# ife18_TS_BMS_Master.net
KiCad netlist of a schematic drawn in Altium Designer
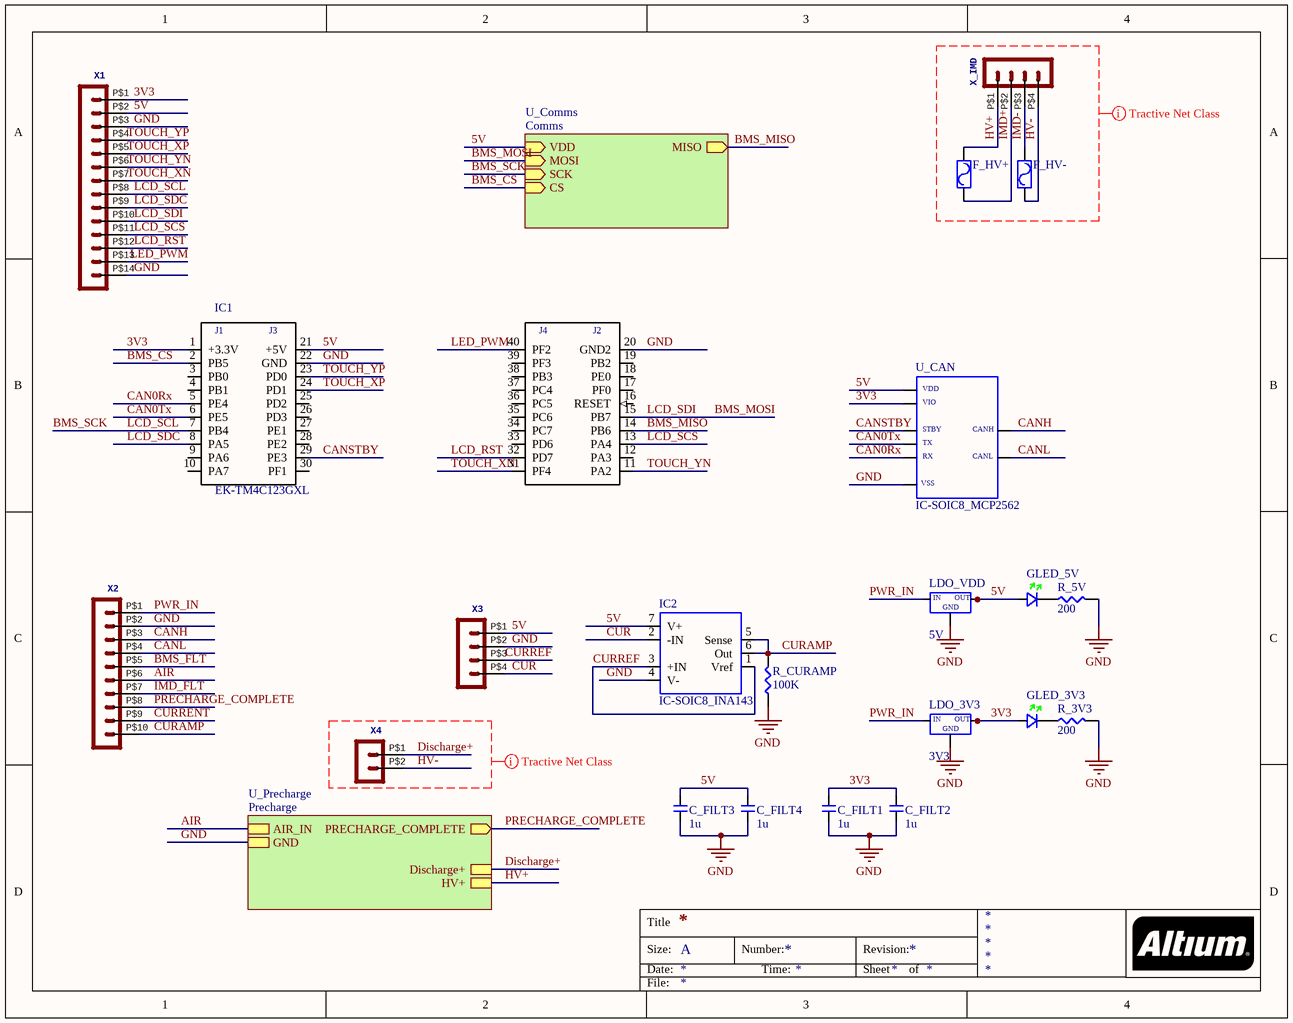
[diagram p0: ife18_TS_BMS_Master.SchDoc]

(export (version "E")
  (design (tool "Eeschema 10.0.6"))
  (components
    (comp (ref "C_FILT1")
      (value "1u")
      (footprint "CAP-0603")
      (libsource (lib "altium-import") (part "root_1_CAP-0603_"))
    )
    (comp (ref "C_FILT2")
      (value "1u")
      (footprint "CAP-0603")
      (libsource (lib "altium-import") (part "root_1_CAP-0603_"))
    )
    (comp (ref "C_FILT3")
      (value "1u")
      (footprint "CAP-0603")
      (libsource (lib "altium-import") (part "root_1_CAP-0603_"))
    )
    (comp (ref "C_FILT4")
      (value "1u")
      (footprint "CAP-0603")
      (libsource (lib "altium-import") (part "root_1_CAP-0603_"))
    )
    (comp (ref "F_HV+")
      (value "~")
      (footprint "FUSE3AG_354101")
      (libsource (lib "altium-import") (part "root_3_FUSE-354101_"))
    )
    (comp (ref "F_HV-")
      (value "~")
      (footprint "FUSE3AG_354101")
      (libsource (lib "altium-import") (part "root_3_FUSE-354101_"))
    )
    (comp (ref "GLED_3V3")
      (value "~")
      (footprint "LEDGREEN-0603")
      (libsource (lib "altium-import") (part "root_0_LEDGREEN-0603_"))
    )
    (comp (ref "GLED_5V")
      (value "~")
      (footprint "LEDGREEN-0603")
      (libsource (lib "altium-import") (part "root_0_LEDGREEN-0603_"))
    )
    (comp (ref "IC1")
      (value "EK-TM4C123GXL")
      (footprint "TM4C123LAUNCHPAD")
      (description "Evaluation Kit For ARM Cortex-M4F-based Microcontrollers")
      (fields (field (name "MF") "Texas Instruments"))
      (libsource (lib "altium-import") (part "root_0_EK-TM4C123GXL_"))
    )
    (comp (ref "IC2")
      (value "IC-SOIC8_INA143")
      (footprint "SOIC8")
      (libsource (lib "altium-import") (part "root_0_IC-SOIC8_INA143_"))
    )
    (comp (ref "LDO_3V3")
      (value "3V3")
      (footprint "SOT223")
      (libsource (lib "altium-import") (part "root_0_LDO-SOT223_SPX1117_"))
    )
    (comp (ref "LDO_VDD")
      (value "5V")
      (footprint "SOT223")
      (libsource (lib "altium-import") (part "root_0_LDO-SOT223_SPX1117_"))
    )
    (comp (ref "R_3V3")
      (value "200")
      (footprint "RES-0603")
      (libsource (lib "altium-import") (part "root_0_RES-0603_"))
    )
    (comp (ref "R_5V")
      (value "200")
      (footprint "RES-0603")
      (libsource (lib "altium-import") (part "root_0_RES-0603_"))
    )
    (comp (ref "R_CURAMP")
      (value "100K")
      (footprint "RES-0603")
      (libsource (lib "altium-import") (part "root_1_RES-0603_"))
    )
    (comp (ref "U_CAN")
      (value "IC-SOIC8_MCP2562")
      (footprint "SOIC8")
      (libsource (lib "altium-import") (part "root_0_IC-SOIC8_MCP2562_"))
    )
    (comp (ref "X1")
      (value "Molex - Micro-Fit 3.0 Series connector,  3.00mm (0.118\") pitch header, 14 positions.")
      (footprint "43045-1418")
      (libsource (lib "altium-import") (part "root_0_mirrored_POS14_MF43045-1418_"))
    )
    (comp (ref "X2")
      (value "Molex - Micro-Fit 3.0 Series connector,  3.00mm (0.118\") pitch header, 10 positions.")
      (footprint "43045-1018")
      (libsource (lib "altium-import") (part "root_0_mirrored_POS10_MF43045-1018_"))
    )
    (comp (ref "X3")
      (value "Molex - Micro-Fit 3.0 Series connector,  3.00mm (0.118\") pitch header, 4 positions.")
      (footprint "43650-0424")
      (libsource (lib "altium-import") (part "root_0_mirrored_POS4_MF43650-0424_"))
    )
    (comp (ref "X4")
      (value "Molex - Micro-Fit 3.0 Series connector,  3.00mm (0.118\") pitch header, 2 positions.")
      (footprint "43650-0224")
      (libsource (lib "altium-import") (part "root_0_mirrored_POS2_MF43650-0224_"))
    )
    (comp (ref "X_IMD")
      (value "~")
      (footprint "43650-0424")
      (libsource (lib "ife19_Elec_Conn_Library") (part "POS4_MF43650-0424"))
    )
  )
  (nets
    (net (code "1") (name "/3V3") (class "Default")
      (node (ref "C_FILT1") (pin "2") (pinfunction "2_2") (pintype "passive"))
      (node (ref "C_FILT2") (pin "2") (pinfunction "2_2") (pintype "passive"))
      (node (ref "GLED_3V3") (pin "A") (pinfunction "A_A") (pintype "passive"))
      (node (ref "IC1") (pin "1") (pinfunction "+3.3V_1") (pintype "power_in"))
      (node (ref "LDO_3V3") (pin "2") (pinfunction "2_2") (pintype "passive"))
      (node (ref "LDO_3V3") (pin "4") (pinfunction "4_4") (pintype "passive"))
      (node (ref "U_CAN") (pin "5") (pinfunction "5_5") (pintype "passive"))
      (node (ref "X1") (pin "P$1") (pinfunction "1_P$1") (pintype "passive"))
    )
    (net (code "2") (name "/5V") (class "Default")
      (node (ref "C_FILT3") (pin "2") (pinfunction "2_2") (pintype "passive"))
      (node (ref "C_FILT4") (pin "2") (pinfunction "2_2") (pintype "passive"))
      (node (ref "GLED_5V") (pin "A") (pinfunction "A_A") (pintype "passive"))
      (node (ref "IC1") (pin "21") (pinfunction "+5V_21") (pintype "power_in"))
      (node (ref "IC2") (pin "7") (pinfunction "V+_7") (pintype "passive"))
      (node (ref "LDO_VDD") (pin "2") (pinfunction "2_2") (pintype "passive"))
      (node (ref "LDO_VDD") (pin "4") (pinfunction "4_4") (pintype "passive"))
      (node (ref "U_CAN") (pin "3") (pinfunction "3_3") (pintype "passive"))
      (node (ref "X1") (pin "P$2") (pinfunction "2_P$2") (pintype "passive"))
      (node (ref "X3") (pin "P$1") (pinfunction "1_P$1") (pintype "passive"))
    )
    (net (code "3") (name "/AIR") (class "Default")
      (node (ref "X2") (pin "P$6") (pinfunction "6_P$6") (pintype "passive"))
    )
    (net (code "4") (name "/BMS_CS") (class "Default")
      (node (ref "IC1") (pin "2") (pinfunction "PB5_2") (pintype "bidirectional"))
    )
    (net (code "5") (name "/BMS_FLT") (class "Default")
      (node (ref "X2") (pin "P$5") (pinfunction "5_P$5") (pintype "passive"))
    )
    (net (code "6") (name "/BMS_MISO") (class "Default")
      (node (ref "IC1") (pin "14") (pinfunction "PB6_14") (pintype "bidirectional"))
    )
    (net (code "7") (name "/BMS_MOSI") (class "Default")
      (node (ref "IC1") (pin "15") (pinfunction "PB7_15") (pintype "bidirectional"))
      (node (ref "X1") (pin "P$10") (pinfunction "10_P$10") (pintype "passive"))
    )
    (net (code "8") (name "/BMS_SCK") (class "Default")
      (node (ref "IC1") (pin "7") (pinfunction "PB4_7") (pintype "bidirectional"))
      (node (ref "X1") (pin "P$8") (pinfunction "8_P$8") (pintype "passive"))
    )
    (net (code "9") (name "/CAN0Rx") (class "Default")
      (node (ref "IC1") (pin "5") (pinfunction "PE4_5") (pintype "bidirectional"))
      (node (ref "U_CAN") (pin "4") (pinfunction "4_4") (pintype "passive"))
    )
    (net (code "10") (name "/CAN0Tx") (class "Default")
      (node (ref "IC1") (pin "6") (pinfunction "PE5_6") (pintype "bidirectional"))
      (node (ref "U_CAN") (pin "1") (pinfunction "1_1") (pintype "passive"))
    )
    (net (code "11") (name "/CANH") (class "Default")
      (node (ref "U_CAN") (pin "7") (pinfunction "7_7") (pintype "passive"))
      (node (ref "X2") (pin "P$3") (pinfunction "3_P$3") (pintype "passive"))
    )
    (net (code "12") (name "/CANL") (class "Default")
      (node (ref "U_CAN") (pin "6") (pinfunction "6_6") (pintype "passive"))
      (node (ref "X2") (pin "P$4") (pinfunction "4_P$4") (pintype "passive"))
    )
    (net (code "13") (name "/CANSTBY") (class "Default")
      (node (ref "IC1") (pin "29") (pinfunction "PE3_29") (pintype "bidirectional"))
      (node (ref "U_CAN") (pin "8") (pinfunction "8_8") (pintype "passive"))
    )
    (net (code "14") (name "/CUR") (class "Default")
      (node (ref "IC2") (pin "2") (pinfunction "-IN_2") (pintype "passive"))
      (node (ref "X3") (pin "P$4") (pinfunction "4_P$4") (pintype "passive"))
    )
    (net (code "15") (name "/CURAMP") (class "Default")
      (node (ref "IC2") (pin "5") (pinfunction "Sense_5") (pintype "passive"))
      (node (ref "IC2") (pin "6") (pinfunction "Out_6") (pintype "passive"))
      (node (ref "R_CURAMP") (pin "2") (pinfunction "2_2") (pintype "passive"))
      (node (ref "X2") (pin "P$10") (pinfunction "10_P$10") (pintype "passive"))
    )
    (net (code "16") (name "/CURREF") (class "Default")
      (node (ref "IC2") (pin "1") (pinfunction "Vref_1") (pintype "passive"))
      (node (ref "IC2") (pin "3") (pinfunction "+IN_3") (pintype "passive"))
      (node (ref "X3") (pin "P$3") (pinfunction "3_P$3") (pintype "passive"))
    )
    (net (code "17") (name "/CURRENT") (class "Default")
      (node (ref "X2") (pin "P$9") (pinfunction "9_P$9") (pintype "passive"))
    )
    (net (code "18") (name "/Discharge+") (class "Default")
      (node (ref "X4") (pin "P$1") (pinfunction "1_P$1") (pintype "passive"))
    )
    (net (code "19") (name "/HV+") (class "Default")
      (node (ref "F_HV+") (pin "2") (pinfunction "2_2") (pintype "passive"))
      (node (ref "X_IMD") (pin "P$1") (pinfunction "1_P$1") (pintype "passive"))
    )
    (net (code "20") (name "/HV-") (class "Default")
      (node (ref "F_HV-") (pin "1") (pinfunction "1_1") (pintype "passive"))
      (node (ref "X4") (pin "P$2") (pinfunction "2_P$2") (pintype "passive"))
      (node (ref "X_IMD") (pin "P$4") (pinfunction "4_P$4") (pintype "passive"))
    )
    (net (code "21") (name "/IMD+") (class "Default")
      (node (ref "F_HV+") (pin "1") (pinfunction "1_1") (pintype "passive"))
      (node (ref "X_IMD") (pin "P$2") (pinfunction "2_P$2") (pintype "passive"))
    )
    (net (code "22") (name "/IMD-") (class "Default")
      (node (ref "F_HV-") (pin "2") (pinfunction "2_2") (pintype "passive"))
      (node (ref "X_IMD") (pin "P$3") (pinfunction "3_P$3") (pintype "passive"))
    )
    (net (code "23") (name "/IMD_FLT") (class "Default")
      (node (ref "X2") (pin "P$7") (pinfunction "7_P$7") (pintype "passive"))
    )
    (net (code "24") (name "/LCD_RST") (class "Default")
      (node (ref "IC1") (pin "32") (pinfunction "PD7_32") (pintype "bidirectional"))
      (node (ref "X1") (pin "P$12") (pinfunction "12_P$12") (pintype "passive"))
    )
    (net (code "25") (name "/LCD_SCS") (class "Default")
      (node (ref "IC1") (pin "13") (pinfunction "PA4_13") (pintype "bidirectional"))
      (node (ref "X1") (pin "P$11") (pinfunction "11_P$11") (pintype "passive"))
    )
    (net (code "26") (name "/LCD_SDC") (class "Default")
      (node (ref "IC1") (pin "8") (pinfunction "PA5_8") (pintype "bidirectional"))
      (node (ref "X1") (pin "P$9") (pinfunction "9_P$9") (pintype "passive"))
    )
    (net (code "27") (name "/LED_PWM") (class "Default")
      (node (ref "IC1") (pin "40") (pinfunction "PF2_40") (pintype "bidirectional"))
      (node (ref "X1") (pin "P$13") (pinfunction "13_P$13") (pintype "passive"))
    )
    (net (code "28") (name "/PRECHARGE_COMPLETE") (class "Default")
      (node (ref "X2") (pin "P$8") (pinfunction "8_P$8") (pintype "passive"))
    )
    (net (code "29") (name "/PWR_IN") (class "Default")
      (node (ref "LDO_3V3") (pin "3") (pinfunction "3_3") (pintype "passive"))
      (node (ref "LDO_VDD") (pin "3") (pinfunction "3_3") (pintype "passive"))
      (node (ref "X2") (pin "P$1") (pinfunction "1_P$1") (pintype "passive"))
    )
    (net (code "30") (name "/TOUCH_XN") (class "Default")
      (node (ref "IC1") (pin "31") (pinfunction "PF4_31") (pintype "bidirectional"))
      (node (ref "X1") (pin "P$7") (pinfunction "7_P$7") (pintype "passive"))
    )
    (net (code "31") (name "/TOUCH_XP") (class "Default")
      (node (ref "IC1") (pin "24") (pinfunction "PD1_24") (pintype "bidirectional"))
      (node (ref "X1") (pin "P$5") (pinfunction "5_P$5") (pintype "passive"))
    )
    (net (code "32") (name "/TOUCH_YN") (class "Default")
      (node (ref "IC1") (pin "11") (pinfunction "PA2_11") (pintype "bidirectional"))
      (node (ref "X1") (pin "P$6") (pinfunction "6_P$6") (pintype "passive"))
    )
    (net (code "33") (name "/TOUCH_YP") (class "Default")
      (node (ref "IC1") (pin "23") (pinfunction "PD0_23") (pintype "bidirectional"))
      (node (ref "X1") (pin "P$4") (pinfunction "4_P$4") (pintype "passive"))
    )
    (net (code "34") (name "GND") (class "Default")
      (node (ref "C_FILT1") (pin "1") (pinfunction "1_1") (pintype "passive"))
      (node (ref "C_FILT2") (pin "1") (pinfunction "1_1") (pintype "passive"))
      (node (ref "C_FILT3") (pin "1") (pinfunction "1_1") (pintype "passive"))
      (node (ref "C_FILT4") (pin "1") (pinfunction "1_1") (pintype "passive"))
      (node (ref "IC1") (pin "20") (pinfunction "GND2_20") (pintype "power_in"))
      (node (ref "IC1") (pin "22") (pinfunction "GND_22") (pintype "power_in"))
      (node (ref "IC2") (pin "4") (pinfunction "V-_4") (pintype "passive"))
      (node (ref "LDO_3V3") (pin "1") (pinfunction "1_1") (pintype "passive"))
      (node (ref "LDO_VDD") (pin "1") (pinfunction "1_1") (pintype "passive"))
      (node (ref "R_3V3") (pin "2") (pinfunction "2_2") (pintype "passive"))
      (node (ref "R_5V") (pin "2") (pinfunction "2_2") (pintype "passive"))
      (node (ref "R_CURAMP") (pin "1") (pinfunction "1_1") (pintype "passive"))
      (node (ref "U_CAN") (pin "2") (pinfunction "2_2") (pintype "passive"))
      (node (ref "X1") (pin "P$14") (pinfunction "14_P$14") (pintype "passive"))
      (node (ref "X1") (pin "P$3") (pinfunction "3_P$3") (pintype "passive"))
      (node (ref "X2") (pin "P$2") (pinfunction "2_P$2") (pintype "passive"))
      (node (ref "X3") (pin "P$2") (pinfunction "2_P$2") (pintype "passive"))
    )
    (net (code "35") (name "Net-(GLED_3V3-PadK)") (class "Default")
      (node (ref "GLED_3V3") (pin "K") (pinfunction "K_K") (pintype "passive"))
      (node (ref "R_3V3") (pin "1") (pinfunction "1_1") (pintype "passive"))
    )
    (net (code "36") (name "Net-(GLED_5V-PadK)") (class "Default")
      (node (ref "GLED_5V") (pin "K") (pinfunction "K_K") (pintype "passive"))
      (node (ref "R_5V") (pin "1") (pinfunction "1_1") (pintype "passive"))
    )
    (net (code "37") (name "unconnected-(IC1-PA3-Pad12)") (class "Default")
      (node (ref "IC1") (pin "12") (pinfunction "PA3_12") (pintype "bidirectional"))
    )
    (net (code "38") (name "unconnected-(IC1-PA6-Pad9)") (class "Default")
      (node (ref "IC1") (pin "9") (pinfunction "PA6_9") (pintype "bidirectional"))
    )
    (net (code "39") (name "unconnected-(IC1-PA7-Pad10)") (class "Default")
      (node (ref "IC1") (pin "10") (pinfunction "PA7_10") (pintype "bidirectional"))
    )
    (net (code "40") (name "unconnected-(IC1-PB0-Pad3)") (class "Default")
      (node (ref "IC1") (pin "3") (pinfunction "PB0_3") (pintype "bidirectional"))
    )
    (net (code "41") (name "unconnected-(IC1-PB1-Pad4)") (class "Default")
      (node (ref "IC1") (pin "4") (pinfunction "PB1_4") (pintype "bidirectional"))
    )
    (net (code "42") (name "unconnected-(IC1-PB2-Pad19)") (class "Default")
      (node (ref "IC1") (pin "19") (pinfunction "PB2_19") (pintype "bidirectional"))
    )
    (net (code "43") (name "unconnected-(IC1-PB3-Pad38)") (class "Default")
      (node (ref "IC1") (pin "38") (pinfunction "PB3_38") (pintype "bidirectional"))
    )
    (net (code "44") (name "unconnected-(IC1-PC4-Pad37)") (class "Default")
      (node (ref "IC1") (pin "37") (pinfunction "PC4_37") (pintype "bidirectional"))
    )
    (net (code "45") (name "unconnected-(IC1-PC5-Pad36)") (class "Default")
      (node (ref "IC1") (pin "36") (pinfunction "PC5_36") (pintype "bidirectional"))
    )
    (net (code "46") (name "unconnected-(IC1-PC6-Pad35)") (class "Default")
      (node (ref "IC1") (pin "35") (pinfunction "PC6_35") (pintype "bidirectional"))
    )
    (net (code "47") (name "unconnected-(IC1-PC7-Pad34)") (class "Default")
      (node (ref "IC1") (pin "34") (pinfunction "PC7_34") (pintype "bidirectional"))
    )
    (net (code "48") (name "unconnected-(IC1-PD2-Pad25)") (class "Default")
      (node (ref "IC1") (pin "25") (pinfunction "PD2_25") (pintype "bidirectional"))
    )
    (net (code "49") (name "unconnected-(IC1-PD3-Pad26)") (class "Default")
      (node (ref "IC1") (pin "26") (pinfunction "PD3_26") (pintype "bidirectional"))
    )
    (net (code "50") (name "unconnected-(IC1-PD6-Pad33)") (class "Default")
      (node (ref "IC1") (pin "33") (pinfunction "PD6_33") (pintype "bidirectional"))
    )
    (net (code "51") (name "unconnected-(IC1-PE0-Pad18)") (class "Default")
      (node (ref "IC1") (pin "18") (pinfunction "PE0_18") (pintype "bidirectional"))
    )
    (net (code "52") (name "unconnected-(IC1-PE1-Pad27)") (class "Default")
      (node (ref "IC1") (pin "27") (pinfunction "PE1_27") (pintype "bidirectional"))
    )
    (net (code "53") (name "unconnected-(IC1-PE2-Pad28)") (class "Default")
      (node (ref "IC1") (pin "28") (pinfunction "PE2_28") (pintype "bidirectional"))
    )
    (net (code "54") (name "unconnected-(IC1-PF0-Pad17)") (class "Default")
      (node (ref "IC1") (pin "17") (pinfunction "PF0_17") (pintype "bidirectional"))
    )
    (net (code "55") (name "unconnected-(IC1-PF1-Pad30)") (class "Default")
      (node (ref "IC1") (pin "30") (pinfunction "PF1_30") (pintype "bidirectional"))
    )
    (net (code "56") (name "unconnected-(IC1-PF3-Pad39)") (class "Default")
      (node (ref "IC1") (pin "39") (pinfunction "PF3_39") (pintype "bidirectional"))
    )
    (net (code "57") (name "unconnected-(IC1-RESET-Pad16)") (class "Default")
      (node (ref "IC1") (pin "16") (pinfunction "RESET_16") (pintype "input"))
    )
  )
)
